# led_demo.net
KiCad netlist of a schematic drawn in EAGLE
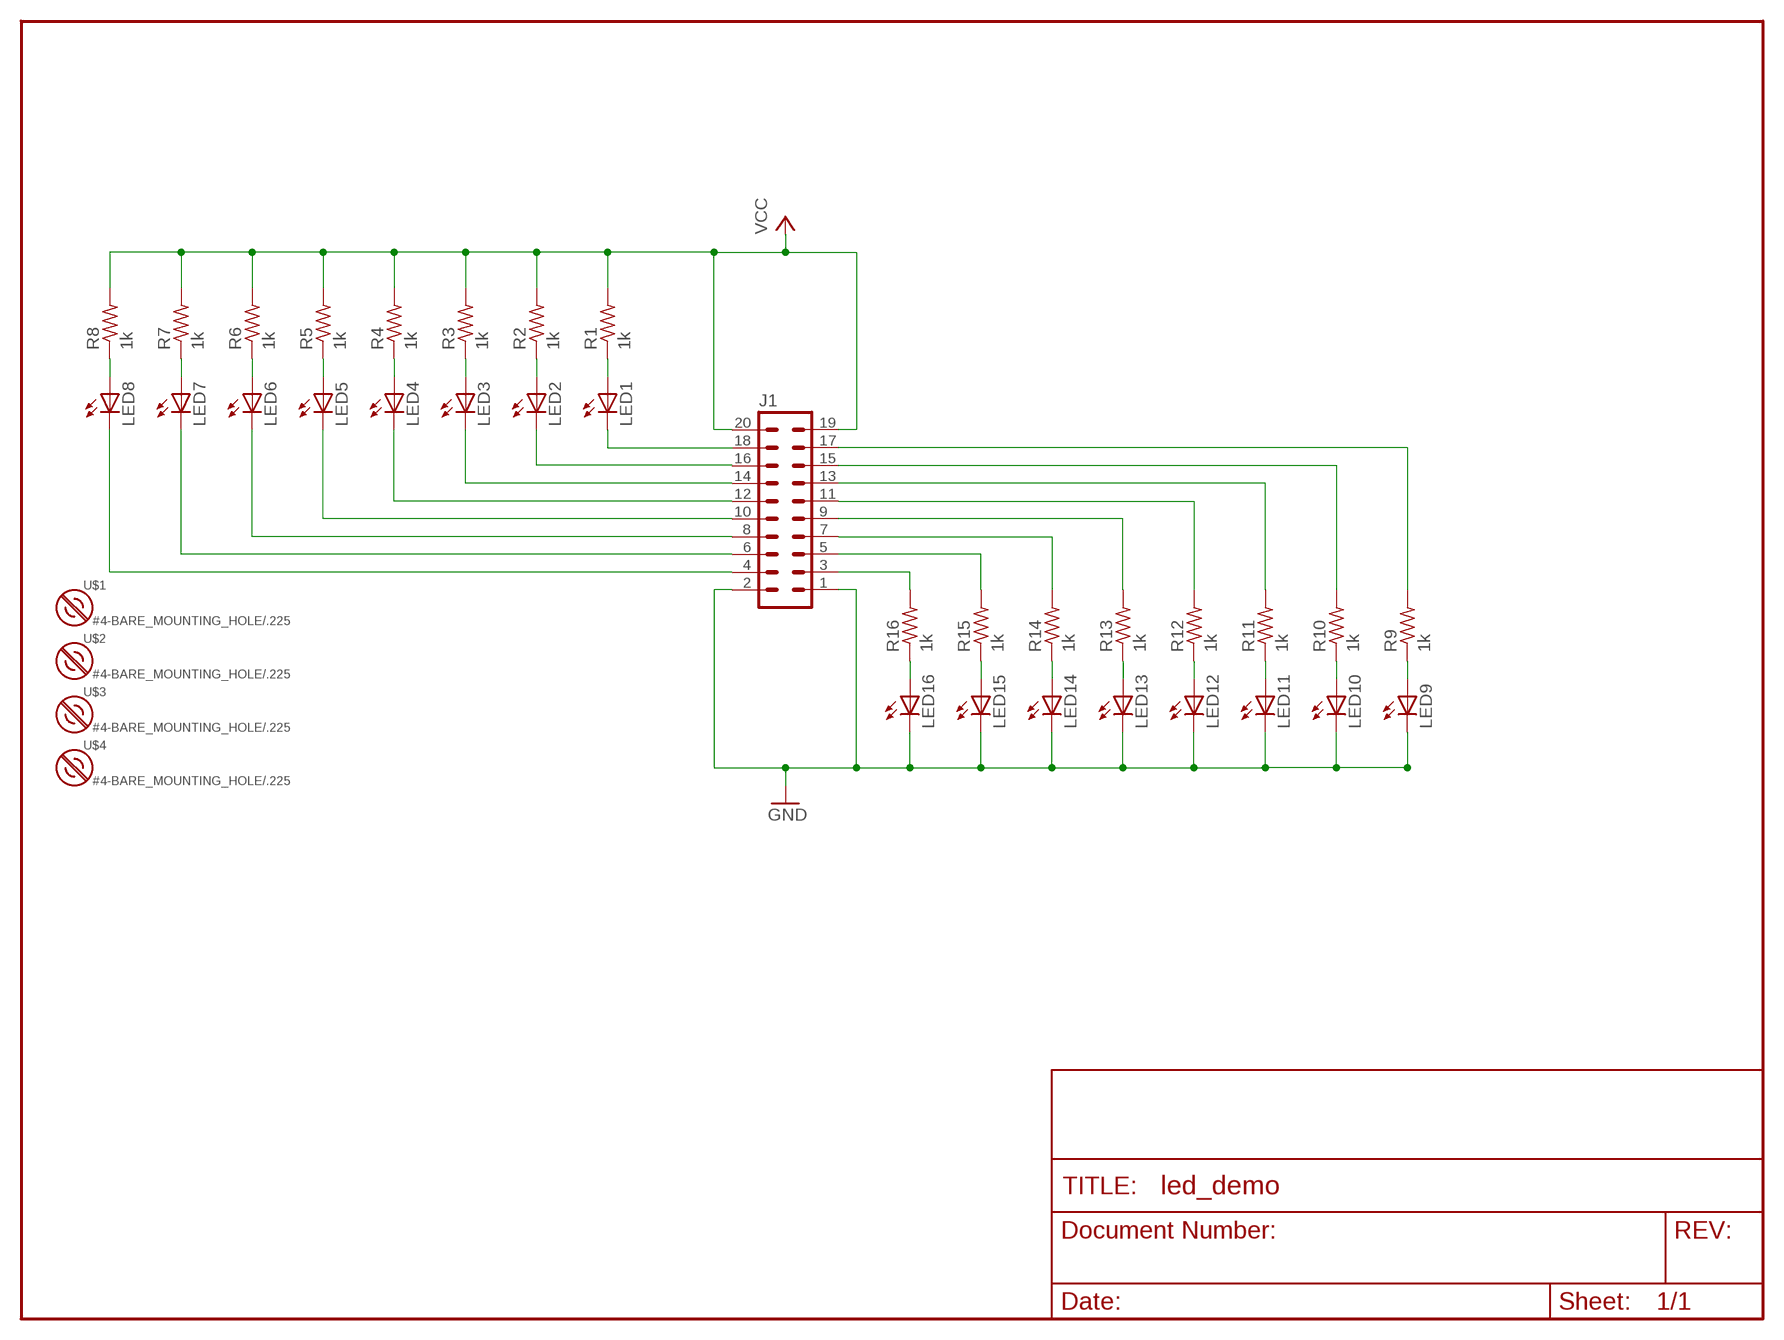
[diagram p0: schematic, sheet 1]

(export (version "E")
  (design (tool "Eeschema 10.0.6"))
  (components
    (comp (ref "J1")
      (value "MA10-2")
      (footprint "eagle-import:MA10-2")
      (libsource (lib "eagle-import") (part "MA10-2"))
    )
    (comp (ref "LED1")
      (value "LED3MM")
      (footprint "eagle-import:LED3MM")
      (libsource (lib "eagle-import") (part "LED3MM"))
    )
    (comp (ref "LED2")
      (value "LED3MM")
      (footprint "eagle-import:LED3MM")
      (libsource (lib "eagle-import") (part "LED3MM"))
    )
    (comp (ref "LED3")
      (value "LED3MM")
      (footprint "eagle-import:LED3MM")
      (libsource (lib "eagle-import") (part "LED3MM"))
    )
    (comp (ref "LED4")
      (value "LED3MM")
      (footprint "eagle-import:LED3MM")
      (libsource (lib "eagle-import") (part "LED3MM"))
    )
    (comp (ref "LED5")
      (value "LED3MM")
      (footprint "eagle-import:LED3MM")
      (libsource (lib "eagle-import") (part "LED3MM"))
    )
    (comp (ref "LED6")
      (value "LED3MM")
      (footprint "eagle-import:LED3MM")
      (libsource (lib "eagle-import") (part "LED3MM"))
    )
    (comp (ref "LED7")
      (value "LED3MM")
      (footprint "eagle-import:LED3MM")
      (libsource (lib "eagle-import") (part "LED3MM"))
    )
    (comp (ref "LED8")
      (value "LED3MM")
      (footprint "eagle-import:LED3MM")
      (libsource (lib "eagle-import") (part "LED3MM"))
    )
    (comp (ref "LED9")
      (value "LED3MM")
      (footprint "eagle-import:LED3MM")
      (libsource (lib "eagle-import") (part "LED3MM"))
    )
    (comp (ref "LED10")
      (value "LED3MM")
      (footprint "eagle-import:LED3MM")
      (libsource (lib "eagle-import") (part "LED3MM"))
    )
    (comp (ref "LED11")
      (value "LED3MM")
      (footprint "eagle-import:LED3MM")
      (libsource (lib "eagle-import") (part "LED3MM"))
    )
    (comp (ref "LED12")
      (value "LED3MM")
      (footprint "eagle-import:LED3MM")
      (libsource (lib "eagle-import") (part "LED3MM"))
    )
    (comp (ref "LED13")
      (value "LED3MM")
      (footprint "eagle-import:LED3MM")
      (libsource (lib "eagle-import") (part "LED3MM"))
    )
    (comp (ref "LED14")
      (value "LED3MM")
      (footprint "eagle-import:LED3MM")
      (libsource (lib "eagle-import") (part "LED3MM"))
    )
    (comp (ref "LED15")
      (value "LED3MM")
      (footprint "eagle-import:LED3MM")
      (libsource (lib "eagle-import") (part "LED3MM"))
    )
    (comp (ref "LED16")
      (value "LED3MM")
      (footprint "eagle-import:LED3MM")
      (libsource (lib "eagle-import") (part "LED3MM"))
    )
    (comp (ref "R1")
      (value "1k")
      (footprint "eagle-import:0204V")
      (libsource (lib "eagle-import") (part "R-US_0204/2V"))
    )
    (comp (ref "R2")
      (value "1k")
      (footprint "eagle-import:0204V")
      (libsource (lib "eagle-import") (part "R-US_0204/2V"))
    )
    (comp (ref "R3")
      (value "1k")
      (footprint "eagle-import:0204V")
      (libsource (lib "eagle-import") (part "R-US_0204/2V"))
    )
    (comp (ref "R4")
      (value "1k")
      (footprint "eagle-import:0204V")
      (libsource (lib "eagle-import") (part "R-US_0204/2V"))
    )
    (comp (ref "R5")
      (value "1k")
      (footprint "eagle-import:0204V")
      (libsource (lib "eagle-import") (part "R-US_0204/2V"))
    )
    (comp (ref "R6")
      (value "1k")
      (footprint "eagle-import:0204V")
      (libsource (lib "eagle-import") (part "R-US_0204/2V"))
    )
    (comp (ref "R7")
      (value "1k")
      (footprint "eagle-import:0204V")
      (libsource (lib "eagle-import") (part "R-US_0204/2V"))
    )
    (comp (ref "R8")
      (value "1k")
      (footprint "eagle-import:0204V")
      (libsource (lib "eagle-import") (part "R-US_0204/2V"))
    )
    (comp (ref "R9")
      (value "1k")
      (footprint "eagle-import:0204V")
      (libsource (lib "eagle-import") (part "R-US_0204/2V"))
    )
    (comp (ref "R10")
      (value "1k")
      (footprint "eagle-import:0204V")
      (libsource (lib "eagle-import") (part "R-US_0204/2V"))
    )
    (comp (ref "R11")
      (value "1k")
      (footprint "eagle-import:0204V")
      (libsource (lib "eagle-import") (part "R-US_0204/2V"))
    )
    (comp (ref "R12")
      (value "1k")
      (footprint "eagle-import:0204V")
      (libsource (lib "eagle-import") (part "R-US_0204/2V"))
    )
    (comp (ref "R13")
      (value "1k")
      (footprint "eagle-import:0204V")
      (libsource (lib "eagle-import") (part "R-US_0204/2V"))
    )
    (comp (ref "R14")
      (value "1k")
      (footprint "eagle-import:0204V")
      (libsource (lib "eagle-import") (part "R-US_0204/2V"))
    )
    (comp (ref "R15")
      (value "1k")
      (footprint "eagle-import:0204V")
      (libsource (lib "eagle-import") (part "R-US_0204/2V"))
    )
    (comp (ref "R16")
      (value "1k")
      (footprint "eagle-import:0204V")
      (libsource (lib "eagle-import") (part "R-US_0204/2V"))
    )
    (comp (ref "U$1")
      (value "#4-BARE_MOUNTING_HOLE/.225")
      (footprint "eagle-import:#4_.225-BARE+HEAD_OR_SMALL_NUT")
      (libsource (lib "eagle-import") (part "#4-BARE_MOUNTING_HOLE/.225"))
    )
    (comp (ref "U$2")
      (value "#4-BARE_MOUNTING_HOLE/.225")
      (footprint "eagle-import:#4_.225-BARE+HEAD_OR_SMALL_NUT")
      (libsource (lib "eagle-import") (part "#4-BARE_MOUNTING_HOLE/.225"))
    )
    (comp (ref "U$3")
      (value "#4-BARE_MOUNTING_HOLE/.225")
      (footprint "eagle-import:#4_.225-BARE+HEAD_OR_SMALL_NUT")
      (libsource (lib "eagle-import") (part "#4-BARE_MOUNTING_HOLE/.225"))
    )
    (comp (ref "U$4")
      (value "#4-BARE_MOUNTING_HOLE/.225")
      (footprint "eagle-import:#4_.225-BARE+HEAD_OR_SMALL_NUT")
      (libsource (lib "eagle-import") (part "#4-BARE_MOUNTING_HOLE/.225"))
    )
  )
  (nets
    (net (code "1") (name "GND") (class "Default")
      (node (ref "J1") (pin "1") (pinfunction "1_1") (pintype "passive"))
      (node (ref "J1") (pin "2") (pinfunction "2_2") (pintype "passive"))
      (node (ref "LED10") (pin "K") (pinfunction "C_K") (pintype "passive"))
      (node (ref "LED11") (pin "K") (pinfunction "C_K") (pintype "passive"))
      (node (ref "LED12") (pin "K") (pinfunction "C_K") (pintype "passive"))
      (node (ref "LED13") (pin "K") (pinfunction "C_K") (pintype "passive"))
      (node (ref "LED14") (pin "K") (pinfunction "C_K") (pintype "passive"))
      (node (ref "LED15") (pin "K") (pinfunction "C_K") (pintype "passive"))
      (node (ref "LED16") (pin "K") (pinfunction "C_K") (pintype "passive"))
      (node (ref "LED9") (pin "K") (pinfunction "C_K") (pintype "passive"))
    )
    (net (code "2") (name "Net-(J1-Pad3)") (class "Default")
      (node (ref "J1") (pin "3") (pinfunction "3_3") (pintype "passive"))
      (node (ref "R16") (pin "2") (pinfunction "2_2") (pintype "passive"))
    )
    (net (code "3") (name "Net-(J1-Pad5)") (class "Default")
      (node (ref "J1") (pin "5") (pinfunction "5_5") (pintype "passive"))
      (node (ref "R15") (pin "2") (pinfunction "2_2") (pintype "passive"))
    )
    (net (code "4") (name "Net-(J1-Pad7)") (class "Default")
      (node (ref "J1") (pin "7") (pinfunction "7_7") (pintype "passive"))
      (node (ref "R14") (pin "2") (pinfunction "2_2") (pintype "passive"))
    )
    (net (code "5") (name "Net-(J1-Pad9)") (class "Default")
      (node (ref "J1") (pin "9") (pinfunction "9_9") (pintype "passive"))
      (node (ref "R13") (pin "2") (pinfunction "2_2") (pintype "passive"))
    )
    (net (code "6") (name "Net-(J1-Pad11)") (class "Default")
      (node (ref "J1") (pin "11") (pinfunction "11_11") (pintype "passive"))
      (node (ref "R12") (pin "2") (pinfunction "2_2") (pintype "passive"))
    )
    (net (code "7") (name "Net-(J1-Pad13)") (class "Default")
      (node (ref "J1") (pin "13") (pinfunction "13_13") (pintype "passive"))
      (node (ref "R11") (pin "2") (pinfunction "2_2") (pintype "passive"))
    )
    (net (code "8") (name "Net-(J1-Pad15)") (class "Default")
      (node (ref "J1") (pin "15") (pinfunction "15_15") (pintype "passive"))
      (node (ref "R10") (pin "2") (pinfunction "2_2") (pintype "passive"))
    )
    (net (code "9") (name "Net-(J1-Pad17)") (class "Default")
      (node (ref "J1") (pin "17") (pinfunction "17_17") (pintype "passive"))
      (node (ref "R9") (pin "2") (pinfunction "2_2") (pintype "passive"))
    )
    (net (code "10") (name "Net-(LED1-C)") (class "Default")
      (node (ref "J1") (pin "18") (pinfunction "18_18") (pintype "passive"))
      (node (ref "LED1") (pin "K") (pinfunction "C_K") (pintype "passive"))
    )
    (net (code "11") (name "Net-(LED1-PadA)") (class "Default")
      (node (ref "LED1") (pin "A") (pinfunction "A_A") (pintype "passive"))
      (node (ref "R1") (pin "1") (pinfunction "1_1") (pintype "passive"))
    )
    (net (code "12") (name "Net-(LED2-C)") (class "Default")
      (node (ref "J1") (pin "16") (pinfunction "16_16") (pintype "passive"))
      (node (ref "LED2") (pin "K") (pinfunction "C_K") (pintype "passive"))
    )
    (net (code "13") (name "Net-(LED2-PadA)") (class "Default")
      (node (ref "LED2") (pin "A") (pinfunction "A_A") (pintype "passive"))
      (node (ref "R2") (pin "1") (pinfunction "1_1") (pintype "passive"))
    )
    (net (code "14") (name "Net-(LED3-C)") (class "Default")
      (node (ref "J1") (pin "14") (pinfunction "14_14") (pintype "passive"))
      (node (ref "LED3") (pin "K") (pinfunction "C_K") (pintype "passive"))
    )
    (net (code "15") (name "Net-(LED3-PadA)") (class "Default")
      (node (ref "LED3") (pin "A") (pinfunction "A_A") (pintype "passive"))
      (node (ref "R3") (pin "1") (pinfunction "1_1") (pintype "passive"))
    )
    (net (code "16") (name "Net-(LED4-C)") (class "Default")
      (node (ref "J1") (pin "12") (pinfunction "12_12") (pintype "passive"))
      (node (ref "LED4") (pin "K") (pinfunction "C_K") (pintype "passive"))
    )
    (net (code "17") (name "Net-(LED4-PadA)") (class "Default")
      (node (ref "LED4") (pin "A") (pinfunction "A_A") (pintype "passive"))
      (node (ref "R4") (pin "1") (pinfunction "1_1") (pintype "passive"))
    )
    (net (code "18") (name "Net-(LED5-C)") (class "Default")
      (node (ref "J1") (pin "10") (pinfunction "10_10") (pintype "passive"))
      (node (ref "LED5") (pin "K") (pinfunction "C_K") (pintype "passive"))
    )
    (net (code "19") (name "Net-(LED5-PadA)") (class "Default")
      (node (ref "LED5") (pin "A") (pinfunction "A_A") (pintype "passive"))
      (node (ref "R5") (pin "1") (pinfunction "1_1") (pintype "passive"))
    )
    (net (code "20") (name "Net-(LED6-C)") (class "Default")
      (node (ref "J1") (pin "8") (pinfunction "8_8") (pintype "passive"))
      (node (ref "LED6") (pin "K") (pinfunction "C_K") (pintype "passive"))
    )
    (net (code "21") (name "Net-(LED6-PadA)") (class "Default")
      (node (ref "LED6") (pin "A") (pinfunction "A_A") (pintype "passive"))
      (node (ref "R6") (pin "1") (pinfunction "1_1") (pintype "passive"))
    )
    (net (code "22") (name "Net-(LED7-C)") (class "Default")
      (node (ref "J1") (pin "6") (pinfunction "6_6") (pintype "passive"))
      (node (ref "LED7") (pin "K") (pinfunction "C_K") (pintype "passive"))
    )
    (net (code "23") (name "Net-(LED7-PadA)") (class "Default")
      (node (ref "LED7") (pin "A") (pinfunction "A_A") (pintype "passive"))
      (node (ref "R7") (pin "1") (pinfunction "1_1") (pintype "passive"))
    )
    (net (code "24") (name "Net-(LED8-C)") (class "Default")
      (node (ref "J1") (pin "4") (pinfunction "4_4") (pintype "passive"))
      (node (ref "LED8") (pin "K") (pinfunction "C_K") (pintype "passive"))
    )
    (net (code "25") (name "Net-(LED8-PadA)") (class "Default")
      (node (ref "LED8") (pin "A") (pinfunction "A_A") (pintype "passive"))
      (node (ref "R8") (pin "1") (pinfunction "1_1") (pintype "passive"))
    )
    (net (code "26") (name "Net-(LED9-PadA)") (class "Default")
      (node (ref "LED9") (pin "A") (pinfunction "A_A") (pintype "passive"))
      (node (ref "R9") (pin "1") (pinfunction "1_1") (pintype "passive"))
    )
    (net (code "27") (name "Net-(LED10-PadA)") (class "Default")
      (node (ref "LED10") (pin "A") (pinfunction "A_A") (pintype "passive"))
      (node (ref "R10") (pin "1") (pinfunction "1_1") (pintype "passive"))
    )
    (net (code "28") (name "Net-(LED11-PadA)") (class "Default")
      (node (ref "LED11") (pin "A") (pinfunction "A_A") (pintype "passive"))
      (node (ref "R11") (pin "1") (pinfunction "1_1") (pintype "passive"))
    )
    (net (code "29") (name "Net-(LED12-PadA)") (class "Default")
      (node (ref "LED12") (pin "A") (pinfunction "A_A") (pintype "passive"))
      (node (ref "R12") (pin "1") (pinfunction "1_1") (pintype "passive"))
    )
    (net (code "30") (name "Net-(LED13-PadA)") (class "Default")
      (node (ref "LED13") (pin "A") (pinfunction "A_A") (pintype "passive"))
      (node (ref "R13") (pin "1") (pinfunction "1_1") (pintype "passive"))
    )
    (net (code "31") (name "Net-(LED14-PadA)") (class "Default")
      (node (ref "LED14") (pin "A") (pinfunction "A_A") (pintype "passive"))
      (node (ref "R14") (pin "1") (pinfunction "1_1") (pintype "passive"))
    )
    (net (code "32") (name "Net-(LED15-PadA)") (class "Default")
      (node (ref "LED15") (pin "A") (pinfunction "A_A") (pintype "passive"))
      (node (ref "R15") (pin "1") (pinfunction "1_1") (pintype "passive"))
    )
    (net (code "33") (name "Net-(LED16-PadA)") (class "Default")
      (node (ref "LED16") (pin "A") (pinfunction "A_A") (pintype "passive"))
      (node (ref "R16") (pin "1") (pinfunction "1_1") (pintype "passive"))
    )
    (net (code "34") (name "VCC") (class "Default")
      (node (ref "J1") (pin "19") (pinfunction "19_19") (pintype "passive"))
      (node (ref "J1") (pin "20") (pinfunction "20_20") (pintype "passive"))
      (node (ref "R1") (pin "2") (pinfunction "2_2") (pintype "passive"))
      (node (ref "R2") (pin "2") (pinfunction "2_2") (pintype "passive"))
      (node (ref "R3") (pin "2") (pinfunction "2_2") (pintype "passive"))
      (node (ref "R4") (pin "2") (pinfunction "2_2") (pintype "passive"))
      (node (ref "R5") (pin "2") (pinfunction "2_2") (pintype "passive"))
      (node (ref "R6") (pin "2") (pinfunction "2_2") (pintype "passive"))
      (node (ref "R7") (pin "2") (pinfunction "2_2") (pintype "passive"))
      (node (ref "R8") (pin "2") (pinfunction "2_2") (pintype "passive"))
    )
  )
)
